# LIS344ALH.net
KiCad netlist of a schematic drawn in EAGLE
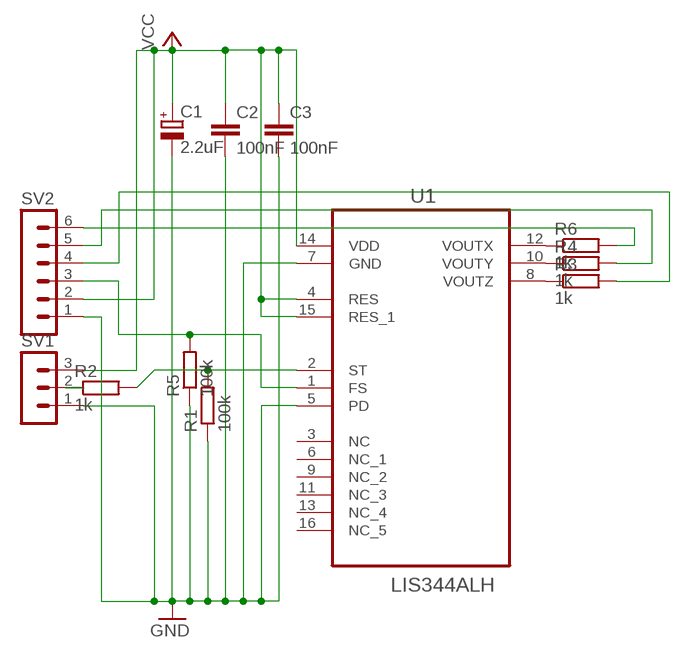
[diagram p0: schematic, sheet 1]

(export (version "E")
  (design (tool "Eeschema 10.0.6"))
  (components
    (comp (ref "C1")
      (value "2.2uF")
      (footprint "eagle-import:E2,5-6E")
      (libsource (lib "eagle-import") (part "CPOL-EUE2,5-6E"))
    )
    (comp (ref "C2")
      (value "100nF")
      (footprint "eagle-import:C2.5-2")
      (libsource (lib "eagle-import") (part "C2.5/2"))
    )
    (comp (ref "C3")
      (value "100nF")
      (footprint "eagle-import:C2.5-2")
      (libsource (lib "eagle-import") (part "C2.5/2"))
    )
    (comp (ref "R1")
      (value "100k")
      (footprint "eagle-import:0204_7")
      (libsource (lib "eagle-import") (part "R-EU_0204/7"))
    )
    (comp (ref "R2")
      (value "1k")
      (footprint "eagle-import:0204_7")
      (libsource (lib "eagle-import") (part "R-EU_0204/7"))
    )
    (comp (ref "R3")
      (value "1k")
      (footprint "eagle-import:0204_7")
      (libsource (lib "eagle-import") (part "R-EU_0204/7"))
    )
    (comp (ref "R4")
      (value "1k")
      (footprint "eagle-import:0204_7")
      (libsource (lib "eagle-import") (part "R-EU_0204/7"))
    )
    (comp (ref "R5")
      (value "100k")
      (footprint "eagle-import:0204_7")
      (libsource (lib "eagle-import") (part "R-EU_0204/7"))
    )
    (comp (ref "R6")
      (value "1k")
      (footprint "eagle-import:0204_7")
      (libsource (lib "eagle-import") (part "R-EU_0204/7"))
    )
    (comp (ref "SV1")
      (value "MA03-1")
      (footprint "eagle-import:MA03-1")
      (libsource (lib "eagle-import") (part "MA03-1"))
    )
    (comp (ref "SV2")
      (value "MA06-1")
      (footprint "eagle-import:MA06-1")
      (libsource (lib "eagle-import") (part "MA06-1"))
    )
    (comp (ref "U1")
      (value "LIS344ALH")
      (footprint "eagle-import:LGA16R65P4X4_400X400X160")
      (fields (field (name "MF") "STMicroelectronics"))
      (libsource (lib "eagle-import") (part "LIS344ALH"))
    )
  )
  (nets
    (net (code "1") (name "GND") (class "Default")
      (node (ref "C1") (pin "-") (pinfunction "-_-") (pintype "passive"))
      (node (ref "C2") (pin "2") (pinfunction "2_2") (pintype "passive"))
      (node (ref "C3") (pin "2") (pinfunction "2_2") (pintype "passive"))
      (node (ref "R1") (pin "1") (pinfunction "1_1") (pintype "passive"))
      (node (ref "R5") (pin "1") (pinfunction "1_1") (pintype "passive"))
      (node (ref "SV1") (pin "1") (pinfunction "1_1") (pintype "passive"))
      (node (ref "SV2") (pin "1") (pinfunction "1_1") (pintype "passive"))
      (node (ref "U1") (pin "5") (pinfunction "PD_5") (pintype "passive"))
      (node (ref "U1") (pin "7") (pinfunction "GND_7") (pintype "passive"))
    )
    (net (code "2") (name "Net-(R2-Pad1)") (class "Default")
      (node (ref "R2") (pin "1") (pinfunction "1_1") (pintype "passive"))
      (node (ref "SV1") (pin "2") (pinfunction "2_2") (pintype "passive"))
    )
    (net (code "3") (name "Net-(R3-Pad2)") (class "Default")
      (node (ref "R3") (pin "2") (pinfunction "2_2") (pintype "passive"))
      (node (ref "SV2") (pin "4") (pinfunction "4_4") (pintype "passive"))
    )
    (net (code "4") (name "Net-(R4-Pad2)") (class "Default")
      (node (ref "R4") (pin "2") (pinfunction "2_2") (pintype "passive"))
      (node (ref "SV2") (pin "5") (pinfunction "5_5") (pintype "passive"))
    )
    (net (code "5") (name "Net-(R6-Pad2)") (class "Default")
      (node (ref "R6") (pin "2") (pinfunction "2_2") (pintype "passive"))
      (node (ref "SV2") (pin "6") (pinfunction "6_6") (pintype "passive"))
    )
    (net (code "6") (name "Net-(U1-FS)") (class "Default")
      (node (ref "R5") (pin "2") (pinfunction "2_2") (pintype "passive"))
      (node (ref "SV2") (pin "3") (pinfunction "3_3") (pintype "passive"))
      (node (ref "U1") (pin "1") (pinfunction "FS_1") (pintype "passive"))
    )
    (net (code "7") (name "Net-(U1-ST)") (class "Default")
      (node (ref "R1") (pin "2") (pinfunction "2_2") (pintype "passive"))
      (node (ref "R2") (pin "2") (pinfunction "2_2") (pintype "passive"))
      (node (ref "U1") (pin "2") (pinfunction "ST_2") (pintype "passive"))
    )
    (net (code "8") (name "Net-(U1-VOUTX)") (class "Default")
      (node (ref "R6") (pin "1") (pinfunction "1_1") (pintype "passive"))
      (node (ref "U1") (pin "12") (pinfunction "VOUTX_12") (pintype "output"))
    )
    (net (code "9") (name "Net-(U1-VOUTY)") (class "Default")
      (node (ref "R4") (pin "1") (pinfunction "1_1") (pintype "passive"))
      (node (ref "U1") (pin "10") (pinfunction "VOUTY_10") (pintype "output"))
    )
    (net (code "10") (name "Net-(U1-VOUTZ)") (class "Default")
      (node (ref "R3") (pin "1") (pinfunction "1_1") (pintype "passive"))
      (node (ref "U1") (pin "8") (pinfunction "VOUTZ_8") (pintype "output"))
    )
    (net (code "11") (name "VCC") (class "Default")
      (node (ref "C1") (pin "+") (pinfunction "+_+") (pintype "passive"))
      (node (ref "C2") (pin "1") (pinfunction "1_1") (pintype "passive"))
      (node (ref "C3") (pin "1") (pinfunction "1_1") (pintype "passive"))
      (node (ref "SV1") (pin "3") (pinfunction "3_3") (pintype "passive"))
      (node (ref "SV2") (pin "2") (pinfunction "2_2") (pintype "passive"))
      (node (ref "U1") (pin "14") (pinfunction "VDD_14") (pintype "power_in"))
      (node (ref "U1") (pin "15") (pinfunction "RES_1_15") (pintype "passive"))
      (node (ref "U1") (pin "4") (pinfunction "RES_4") (pintype "passive"))
    )
    (net (code "12") (name "unconnected-(U1-NC-Pad3)") (class "Default")
      (node (ref "U1") (pin "3") (pinfunction "NC_3") (pintype "no_connect"))
    )
    (net (code "13") (name "unconnected-(U1-NC_1-Pad6)") (class "Default")
      (node (ref "U1") (pin "6") (pinfunction "NC_1_6") (pintype "no_connect"))
    )
    (net (code "14") (name "unconnected-(U1-NC_2-Pad9)") (class "Default")
      (node (ref "U1") (pin "9") (pinfunction "NC_2_9") (pintype "no_connect"))
    )
    (net (code "15") (name "unconnected-(U1-NC_3-Pad11)") (class "Default")
      (node (ref "U1") (pin "11") (pinfunction "NC_3_11") (pintype "no_connect"))
    )
    (net (code "16") (name "unconnected-(U1-NC_4-Pad13)") (class "Default")
      (node (ref "U1") (pin "13") (pinfunction "NC_4_13") (pintype "no_connect"))
    )
    (net (code "17") (name "unconnected-(U1-NC_5-Pad16)") (class "Default")
      (node (ref "U1") (pin "16") (pinfunction "NC_5_16") (pintype "no_connect"))
    )
  )
)
